# Power.net
KiCad netlist of a schematic drawn in Altium Designer
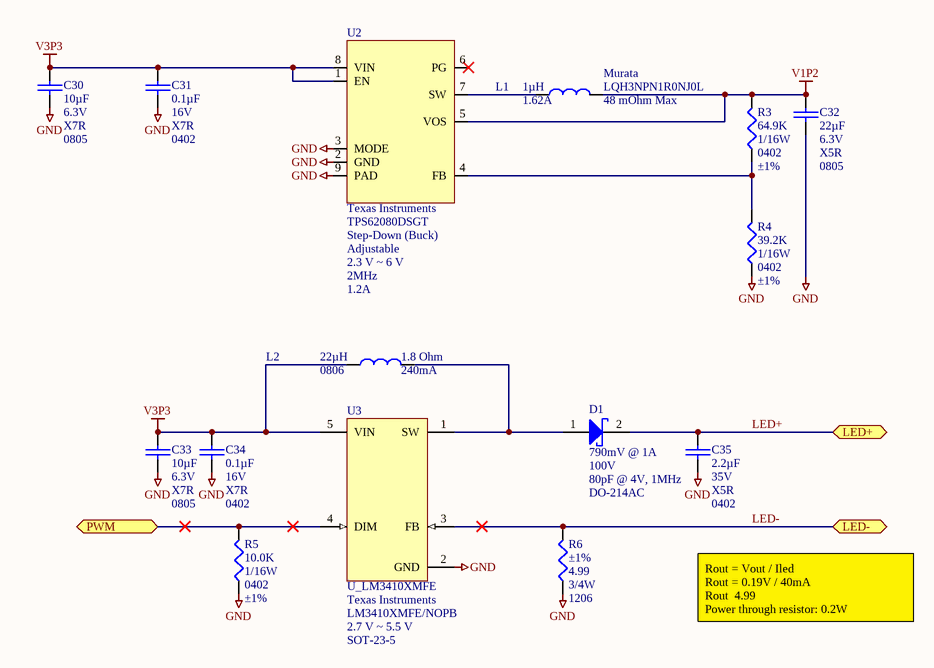
[diagram p0: Power.SchDoc]

(export (version "E")
  (design (tool "Eeschema 10.0.6"))
  (components
    (comp (ref "C30")
      (value "10uF")
      (footprint "C_ERA-0805")
      (description "CAP CER 10UF 6.3V X7R 10% 0805")
      (fields
        (field (name "MANUFACTURER") "Taiyo Yuden")
        (field (name "MANUFACTURER PART NUMBER") "JMK212BJ106KD-T")
        (field (name "CAPACITANCE") "10µF")
        (field (name "VOLTAGE - RATED") "6.3V")
        (field (name "TEMPERATURE COEFFICIENT") "X7R")
        (field (name "PACKAGE / CASE") "0805")
      )
      (libsource (lib "Main LibraryX") (part "C_0805_10UF_6.3V"))
    )
    (comp (ref "C31")
      (value "0.1uF")
      (footprint "C_0402")
      (description "CAP CER .10UF 16V X7R 0402")
      (fields
        (field (name "MANUFACTURER") "TDK Corporation")
        (field (name "MANUFACTURER PART NUMBER") "C1005X7R1C104K050BC")
        (field (name "CAPACITANCE") "0.1µF")
        (field (name "VOLTAGE - RATED") "16V")
        (field (name "TEMPERATURE COEFFICIENT") "X7R")
        (field (name "PACKAGE / CASE") "0402")
      )
      (libsource (lib "Main LibraryX") (part "C_0402_0.1UF_16V"))
    )
    (comp (ref "C32")
      (value "22uF")
      (footprint "C_ERA-0805")
      (description "CAP CER 22UF 6.3V X7R 10% 0805")
      (fields
        (field (name "MANUFACTURER") "Samsung Electro-Mechanics America, Inc")
        (field (name "MANUFACTURER PART NUMBER") "CL21A226MQQNNNE")
        (field (name "CAPACITANCE") "22µF")
        (field (name "VOLTAGE - RATED") "6.3V")
        (field (name "TEMPERATURE COEFFICIENT") "X5R")
        (field (name "PACKAGE / CASE") "0805")
      )
      (libsource (lib "Main LibraryX") (part "C_0805_22UF_6.3V"))
    )
    (comp (ref "C33")
      (value "10uF")
      (footprint "C_ERA-0805")
      (description "CAP CER 10UF 6.3V X7R 10% 0805")
      (fields
        (field (name "MANUFACTURER") "Taiyo Yuden")
        (field (name "MANUFACTURER PART NUMBER") "JMK212BJ106KD-T")
        (field (name "CAPACITANCE") "10µF")
        (field (name "VOLTAGE - RATED") "6.3V")
        (field (name "TEMPERATURE COEFFICIENT") "X7R")
        (field (name "PACKAGE / CASE") "0805")
      )
      (libsource (lib "Main LibraryX") (part "C_0805_10UF_6.3V"))
    )
    (comp (ref "C34")
      (value "0.1uF")
      (footprint "C_0402")
      (description "CAP CER .10UF 16V X7R 0402")
      (fields
        (field (name "MANUFACTURER") "TDK Corporation")
        (field (name "MANUFACTURER PART NUMBER") "C1005X7R1C104K050BC")
        (field (name "CAPACITANCE") "0.1µF")
        (field (name "VOLTAGE - RATED") "16V")
        (field (name "TEMPERATURE COEFFICIENT") "X7R")
        (field (name "PACKAGE / CASE") "0402")
      )
      (libsource (lib "Main LibraryX") (part "C_0402_0.1UF_16V"))
    )
    (comp (ref "C35")
      (value "C_0402_2.2uF_35V")
      (footprint "C_ERA-0402")
      (description "CAP CER 2.2UF 35V 20% X5R 0402")
      (fields
        (field (name "CAPACITANCE") "2.2µF")
        (field (name "VOLTAGE - RATED") "35V")
        (field (name "TEMPERATURE COEFFICIENT") "X5R")
        (field (name "PACKAGE / CASE") "0402")
        (field (name "MANUFACTURER") "TDK Corporation")
        (field (name "MANUFACTURER PART NUMBER") "C1005X5R1V225M050BC")
      )
      (libsource (lib "Main LibraryX") (part "C_0402_2.2uF_35V"))
    )
    (comp (ref "D1")
      (value "B1100-13-F")
      (footprint "DIOM5226X23L")
      (description "DIODE SCHOTTKY 100V 1A SMA")
      (fields
        (field (name "MANUFACTURER") "Diodes Inc")
        (field (name "VOLTAGE - FORWARD (VF) (MAX) @ IF") "790mV @ 1A")
        (field (name "VOLTAGE - DC REVERSE (VR) (MAX)") "100V")
        (field (name "CAPACITANCE @ VR, F") "80pF @ 4V, 1MHz")
        (field (name "PACKAGE / CASE") "DO-214AC")
      )
      (libsource (lib "Main Library") (part "D_SCHOTT_B1100-13-F"))
    )
    (comp (ref "L1")
      (value "1.0uH")
      (footprint "INDNRH1212")
      (description "INDUCTOR POWER 1.0UH 1620MA 1212")
      (fields
        (field (name "TOLERANCE") "±30%")
        (field (name "MANUFACTURER PART NUMBER") "LQH3NPN1R0NJ0L")
        (field (name "INDUCTANCE") "1µH")
        (field (name "CURRENT") "1.62A")
        (field (name "DC RESISTANCE (DCR)") "48 mOhm Max")
        (field (name "MANUFACTURER") "Murata")
      )
      (libsource (lib "Main Library") (part "L_1.0UH_1.62A"))
    )
    (comp (ref "L2")
      (value "CBC2016T220K")
      (footprint "L_0806")
      (description "INDUCTOR 22UH 10% 0806 SMD")
      (fields
        (field (name "MANUFACTURER") "Taiyo Yuden")
        (field (name "TOLERANCE") "±10%")
        (field (name "CURRENT") "240mA")
        (field (name "PACKAGE / CASE") "0806")
        (field (name "INDUCTANCE") "22µH")
        (field (name "DC RESISTANCE (DCR)") "1.8 Ohm")
      )
      (libsource (lib "Main Library") (part "L_0806_22uH"))
    )
    (comp (ref "R3")
      (value "R_0402_64.9K")
      (footprint "ERA-0402")
      (description "RES 64.9K OHM 1/16W 1% 0402 SMD")
      (fields
        (field (name "MANUFACTURER") "Yageo")
        (field (name "MANUFACTURER PART NUMBER") "RC0402FR-0764K9L")
        (field (name "RESISTANCE IN OHMS") "64.9K")
        (field (name "POWER (WATTS)") "1/16W")
        (field (name "CASE") "0402")
        (field (name "TOLERANCE") "±1%")
      )
      (libsource (lib "Main Library") (part "R_0402_64.9K"))
    )
    (comp (ref "R4")
      (value "R_0402_39.2K")
      (footprint "ERA-0402")
      (description "RES 39.2K OHM 1/16W 1% 0402 SMD")
      (fields
        (field (name "RESISTANCE IN OHMS") "39.2K")
        (field (name "POWER (WATTS)") "1/16W")
        (field (name "CASE") "0402")
        (field (name "TOLERANCE") "±1%")
        (field (name "MANUFACTURER") "Yageo")
        (field (name "MANUFACTURER PART NUMBER") "RC0402FR-0739K2L")
      )
      (libsource (lib "Main LibraryX") (part "R_0402_39.2K"))
    )
    (comp (ref "R5")
      (value "R_0402_10.0K")
      (footprint "R_0402")
      (description "RES 10.0K OHM 1/16W 1% 0402 SMD")
      (fields
        (field (name "MANUFACTURER") "Stackpole Electronics Inc")
        (field (name "MANUFACTURER PART NUMBER") "RMCF0402FT10K0")
        (field (name "RESISTANCE IN OHMS") "10.0K")
        (field (name "POWER (WATTS)") "1/16W")
        (field (name "CASE") "0402")
        (field (name "TOLERANCE") "±1%")
      )
      (libsource (lib "Cospan Design") (part "R_0402_10.0K"))
    )
    (comp (ref "R6")
      (value "R_1206_4.99")
      (footprint "R_1206")
      (description "RES SMD 4.99 OHM 1% 3/4W 1206")
      (fields
        (field (name "MANUFACTURER") "Vishay / Dale")
        (field (name "MANUFACTURER PART NUMBER") "CRCW12064R99FKEAHP")
        (field (name "TOLERANCE") "±1%")
        (field (name "RESISTANCE IN OHMS") "4.99")
        (field (name "POWER (WATTS)") "3/4W")
        (field (name "CASE") "1206")
      )
      (libsource (lib "Cospan Design") (part "R_1206_4.99"))
    )
    (comp (ref "U2")
      (value "TPS62080")
      (footprint "QFN50P200X200X80-8L")
      (description "IC BUCK SYNC ADJ 1.2A 8WSON")
      (fields
        (field (name "MANUFACTURER") "Texas Instruments")
        (field (name "MANUFACTURER PART NUMBER") "TPS62080DSGT")
        (field (name "TYPE") "Step-Down (Buck)")
        (field (name "OUTPUT TYPE") "Adjustable")
        (field (name "VOLTAGE - INPUT") "2.3 V ~ 6 V")
        (field (name "FREQUENCY - SWITCHING") "2MHz")
        (field (name "CURRENT - OUTPUT") "1.2A")
      )
      (libsource (lib "Main Library") (part "U_TPS62080"))
    )
    (comp (ref "U3")
      (value "U_LM3410XMFE")
      (footprint "MF05A_N")
      (description "IC DRVR WT/OLED BCKLT SOT23-5")
      (fields
        (field (name "MANUFACTURER") "Texas Instruments")
        (field (name "MANUFACTURER PART NUMBER") "LM3410XMFE/NOPB")
        (field (name "VOLTAGE - SUPPLY") "2.7 V ~ 5.5 V")
        (field (name "SUPPLIER DEVICE PACKAGE") "SOT-23-5")
      )
      (libsource (lib "Main Library") (part "U_LM3410XMFE"))
    )
  )
  (nets
    (net (code "1") (name "/LED+") (class "Default")
      (node (ref "C35") (pin "2") (pinfunction "2_2") (pintype "passive"))
      (node (ref "D1") (pin "2") (pinfunction "K_2") (pintype "passive"))
    )
    (net (code "2") (name "/LED-") (class "Default")
      (node (ref "R6") (pin "1") (pinfunction "1_1") (pintype "passive"))
      (node (ref "U3") (pin "3") (pinfunction "FB_3") (pintype "input"))
    )
    (net (code "3") (name "/PWM") (class "Default")
      (node (ref "R5") (pin "1") (pinfunction "1_1") (pintype "passive"))
      (node (ref "U3") (pin "4") (pinfunction "DIM_4") (pintype "input"))
    )
    (net (code "4") (name "GND") (class "Default")
      (node (ref "C30") (pin "1") (pinfunction "1_1") (pintype "passive"))
      (node (ref "C31") (pin "1") (pinfunction "1_1") (pintype "passive"))
      (node (ref "C32") (pin "1") (pinfunction "1_1") (pintype "passive"))
      (node (ref "C33") (pin "1") (pinfunction "1_1") (pintype "passive"))
      (node (ref "C34") (pin "1") (pinfunction "1_1") (pintype "passive"))
      (node (ref "C35") (pin "1") (pinfunction "1_1") (pintype "passive"))
      (node (ref "R4") (pin "2") (pinfunction "2_2") (pintype "passive"))
      (node (ref "R5") (pin "2") (pinfunction "2_2") (pintype "passive"))
      (node (ref "R6") (pin "2") (pinfunction "2_2") (pintype "passive"))
      (node (ref "U2") (pin "2") (pinfunction "GND_2") (pintype "passive"))
      (node (ref "U2") (pin "3") (pinfunction "MODE_3") (pintype "passive"))
      (node (ref "U2") (pin "9") (pinfunction "PAD_9") (pintype "passive"))
      (node (ref "U3") (pin "2") (pinfunction "GND_2") (pintype "power_in"))
    )
    (net (code "5") (name "Net-(D1-A)") (class "Default")
      (node (ref "D1") (pin "1") (pinfunction "A_1") (pintype "passive"))
      (node (ref "L2") (pin "2") (pintype "passive"))
      (node (ref "U3") (pin "1") (pinfunction "SW_1") (pintype "power_in"))
    )
    (net (code "6") (name "Net-(U2-FB)") (class "Default")
      (node (ref "R3") (pin "2") (pinfunction "2_2") (pintype "passive"))
      (node (ref "R4") (pin "1") (pinfunction "1_1") (pintype "passive"))
      (node (ref "U2") (pin "4") (pinfunction "FB_4") (pintype "passive"))
    )
    (net (code "7") (name "Net-(U2-SW)") (class "Default")
      (node (ref "L1") (pin "1") (pintype "passive"))
      (node (ref "U2") (pin "7") (pinfunction "SW_7") (pintype "passive"))
    )
    (net (code "8") (name "V1P2") (class "Default")
      (node (ref "C32") (pin "2") (pinfunction "2_2") (pintype "passive"))
      (node (ref "L1") (pin "2") (pintype "passive"))
      (node (ref "R3") (pin "1") (pinfunction "1_1") (pintype "passive"))
      (node (ref "U2") (pin "5") (pinfunction "VOS_5") (pintype "passive"))
    )
    (net (code "9") (name "V3P3") (class "Default")
      (node (ref "C30") (pin "2") (pinfunction "2_2") (pintype "passive"))
      (node (ref "C31") (pin "2") (pinfunction "2_2") (pintype "passive"))
      (node (ref "C33") (pin "2") (pinfunction "2_2") (pintype "passive"))
      (node (ref "C34") (pin "2") (pinfunction "2_2") (pintype "passive"))
      (node (ref "L2") (pin "1") (pintype "passive"))
      (node (ref "U2") (pin "1") (pinfunction "EN_1") (pintype "passive"))
      (node (ref "U2") (pin "8") (pinfunction "VIN_8") (pintype "passive"))
      (node (ref "U3") (pin "5") (pinfunction "VIN_5") (pintype "power_in"))
    )
    (net (code "10") (name "unconnected-(U2-PG-Pad6)") (class "Default")
      (node (ref "U2") (pin "6") (pinfunction "PG_6") (pintype "passive+no_connect"))
    )
  )
)
